# WebCamera.net
KiCad netlist of a schematic drawn in Altium Designer
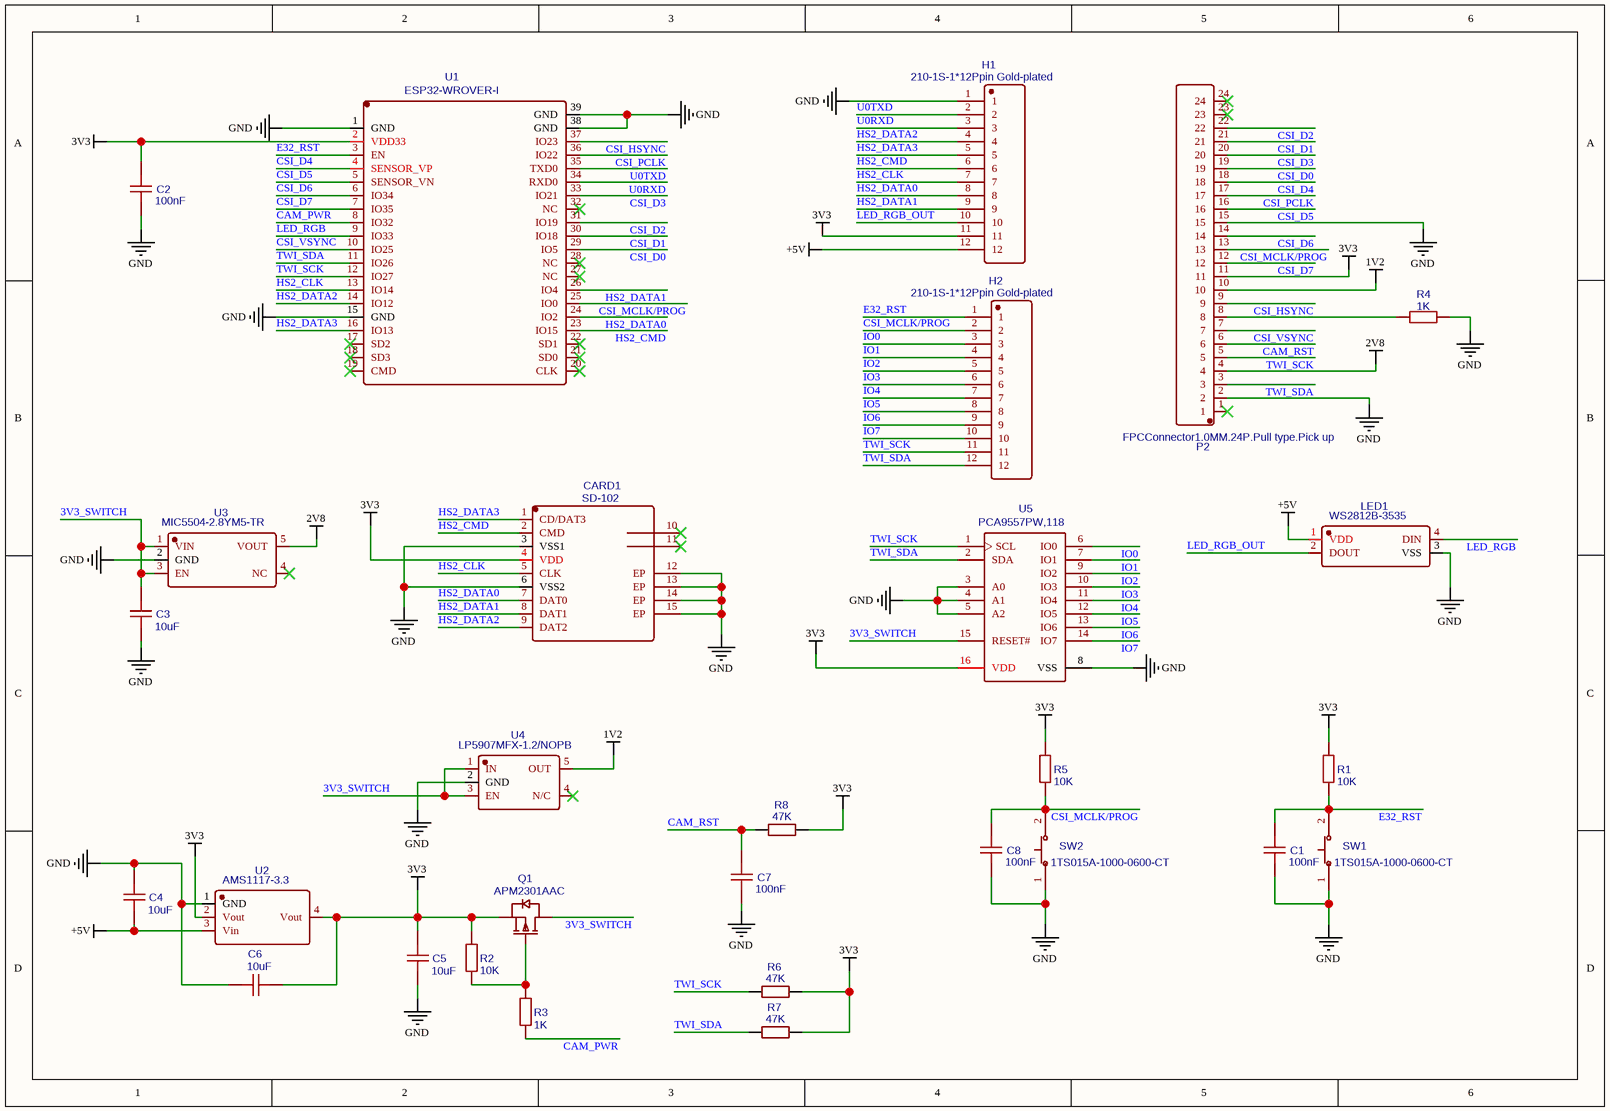
[diagram p0: WebCamera.schdoc]

(export (version "E")
  (design (tool "Eeschema 10.0.6"))
  (components
    (comp (ref "C1")
      (value "100nF")
      (fields
        (field (name "BOM_SUPPLIER PART") "C307331")
        (field (name "BOM_MANUFACTURER PART") "CL05B104KB54PNC")
        (field (name "CONTRIBUTOR") "LCSC")
      )
      (libsource (lib "altium-import") (part "root_1_100nF_"))
    )
    (comp (ref "C2")
      (value "100nF")
      (fields
        (field (name "BOM_SUPPLIER PART") "C307331")
        (field (name "BOM_MANUFACTURER PART") "CL05B104KB54PNC")
        (field (name "CONTRIBUTOR") "LCSC")
      )
      (libsource (lib "altium-import") (part "root_1_100nF_"))
    )
    (comp (ref "C3")
      (value "10uF")
      (fields
        (field (name "BOM_MANUFACTURER PART") "CL10A106KP8NNNC")
        (field (name "BOM_SUPPLIER PART") "C19702")
      )
      (libsource (lib "altium-import") (part "root_1_10uF_"))
    )
    (comp (ref "C4")
      (value "10uF")
      (fields
        (field (name "BOM_MANUFACTURER PART") "CL10A106KP8NNNC")
        (field (name "BOM_SUPPLIER PART") "C19702")
      )
      (libsource (lib "altium-import") (part "root_1_10uF_"))
    )
    (comp (ref "C5")
      (value "10uF")
      (fields
        (field (name "BOM_MANUFACTURER PART") "CL10A106KP8NNNC")
        (field (name "BOM_SUPPLIER PART") "C19702")
      )
      (libsource (lib "altium-import") (part "root_1_10uF_"))
    )
    (comp (ref "C6")
      (value "10uF")
      (fields
        (field (name "BOM_MANUFACTURER PART") "CL10A106KP8NNNC")
        (field (name "BOM_SUPPLIER PART") "C19702")
      )
      (libsource (lib "altium-import") (part "root_2_10uF_"))
    )
    (comp (ref "C7")
      (value "100nF")
      (fields
        (field (name "BOM_SUPPLIER PART") "C307331")
        (field (name "BOM_MANUFACTURER PART") "CL05B104KB54PNC")
        (field (name "CONTRIBUTOR") "LCSC")
      )
      (libsource (lib "altium-import") (part "root_1_100nF_"))
    )
    (comp (ref "C8")
      (value "100nF")
      (fields
        (field (name "BOM_SUPPLIER PART") "C307331")
        (field (name "BOM_MANUFACTURER PART") "CL05B104KB54PNC")
        (field (name "CONTRIBUTOR") "LCSC")
      )
      (libsource (lib "altium-import") (part "root_1_100nF_"))
    )
    (comp (ref "CARD1")
      (value "SD-102")
      (fields (field (name "BOM_SUPPLIER PART") "C266602") (field (name "CONTRIBUTOR") "LCSC"))
      (libsource (lib "altium-import") (part "root_0_SD-102_"))
    )
    (comp (ref "H1")
      (value "210-1S-1*12Ppin Gold-plated")
      (fields (field (name "BOM_SUPPLIER PART") "C124353") (field (name "CONTRIBUTOR") "LCSC"))
      (libsource (lib "altium-import") (part "root_0_210-1S-1*12Ppin Gold-plated_"))
    )
    (comp (ref "H2")
      (value "210-1S-1*12Ppin Gold-plated")
      (fields (field (name "BOM_SUPPLIER PART") "C124353") (field (name "CONTRIBUTOR") "LCSC"))
      (libsource (lib "altium-import") (part "root_0_210-1S-1*12Ppin Gold-plated_"))
    )
    (comp (ref "LED1")
      (value "WS2812B-3535")
      (fields (field (name "BOM_SUPPLIER PART") "C114583") (field (name "CONTRIBUTOR") "LCSC"))
      (libsource (lib "altium-import") (part "root_0_WS2812B-3535_"))
    )
    (comp (ref "P2")
      (value "FPCConnector1.0MM.24P.Pull type.Pick up")
      (fields (field (name "BOM_SUPPLIER PART") "C34750"))
      (libsource (lib "altium-import") (part "root_0_FPCConnector1.0MM.24P.Pull type.Pick up_"))
    )
    (comp (ref "Q1")
      (value "APM2301AAC")
      (fields (field (name "BOM_SUPPLIER PART") "C475607") (field (name "CONTRIBUTOR") "LCSC"))
      (libsource (lib "altium-import") (part "root_1_APM2301AAC_"))
    )
    (comp (ref "R1")
      (value "10K")
      (fields
        (field (name "BOM_SUPPLIER PART") "C380776")
        (field (name "BOM_MANUFACTURER PART") "SY0805JN10KP")
        (field (name "CONTRIBUTOR") "LCSC")
      )
      (libsource (lib "altium-import") (part "root_1_10K_"))
    )
    (comp (ref "R2")
      (value "10K")
      (fields
        (field (name "BOM_SUPPLIER PART") "C380776")
        (field (name "BOM_MANUFACTURER PART") "SY0805JN10KP")
        (field (name "CONTRIBUTOR") "LCSC")
      )
      (libsource (lib "altium-import") (part "root_1_10K_"))
    )
    (comp (ref "R3")
      (value "1K")
      (fields
        (field (name "BOM_SUPPLIER PART") "C328385")
        (field (name "BOM_MANUFACTURER PART") "AECR0805F1K00K9")
        (field (name "CONTRIBUTOR") "LCSC")
      )
      (libsource (lib "altium-import") (part "root_1_1K_"))
    )
    (comp (ref "R4")
      (value "1K")
      (fields
        (field (name "BOM_SUPPLIER PART") "C328385")
        (field (name "BOM_MANUFACTURER PART") "AECR0805F1K00K9")
        (field (name "CONTRIBUTOR") "LCSC")
      )
      (libsource (lib "altium-import") (part "root_2_1K_"))
    )
    (comp (ref "R5")
      (value "10K")
      (fields
        (field (name "BOM_SUPPLIER PART") "C380776")
        (field (name "BOM_MANUFACTURER PART") "SY0805JN10KP")
        (field (name "CONTRIBUTOR") "LCSC")
      )
      (libsource (lib "altium-import") (part "root_1_10K_"))
    )
    (comp (ref "R6")
      (value "47K")
      (fields
        (field (name "BOM_MANUFACTURER PART") "CR0805J80473G")
        (field (name "BOM_SUPPLIER PART") "C102018")
      )
      (libsource (lib "altium-import") (part "root_0_47K_"))
    )
    (comp (ref "R7")
      (value "47K")
      (fields
        (field (name "BOM_MANUFACTURER PART") "CR0805J80473G")
        (field (name "BOM_SUPPLIER PART") "C102018")
      )
      (libsource (lib "altium-import") (part "root_0_47K_"))
    )
    (comp (ref "R8")
      (value "47K")
      (fields
        (field (name "BOM_MANUFACTURER PART") "CR0805J80473G")
        (field (name "BOM_SUPPLIER PART") "C102018")
      )
      (libsource (lib "altium-import") (part "root_0_47K_"))
    )
    (comp (ref "SW1")
      (value "1TS015A-1000-0600-CT")
      (fields (field (name "BOM_SUPPLIER PART") "C398744") (field (name "CONTRIBUTOR") "LCSC"))
      (libsource (lib "altium-import") (part "root_1_1TS015A-1000-0600-CT_"))
    )
    (comp (ref "SW2")
      (value "1TS015A-1000-0600-CT")
      (fields (field (name "BOM_SUPPLIER PART") "C398744") (field (name "CONTRIBUTOR") "LCSC"))
      (libsource (lib "altium-import") (part "root_1_1TS015A-1000-0600-CT_"))
    )
    (comp (ref "U1")
      (value "ESP32-WROVER-I")
      (fields (field (name "BOM_SUPPLIER PART") "C132370") (field (name "CONTRIBUTOR") "LCSC"))
      (libsource (lib "altium-import") (part "root_0_ESP32-WROVER-I_"))
    )
    (comp (ref "U2")
      (value "AMS1117-3.3")
      (fields (field (name "BOM_SUPPLIER PART") "C6186"))
      (libsource (lib "altium-import") (part "root_0_AMS1117-3.3_"))
    )
    (comp (ref "U3")
      (value "MIC5504-2.8YM5-TR")
      (fields (field (name "BOM_SUPPLIER PART") "C95749") (field (name "CONTRIBUTOR") "LCSC"))
      (libsource (lib "altium-import") (part "root_0_MIC5504-2.8YM5-TR_"))
    )
    (comp (ref "U4")
      (value "LP5907MFX-1.2/NOPB")
      (fields (field (name "BOM_SUPPLIER PART") "C73478") (field (name "CONTRIBUTOR") "LCSC"))
      (libsource (lib "altium-import") (part "root_0_LP5907MFX-1.2/NOPB_"))
    )
    (comp (ref "U5")
      (value "PCA9557PW,118")
      (fields (field (name "BOM_SUPPLIER PART") "C141380") (field (name "CONTRIBUTOR") "LCSC"))
      (libsource (lib "altium-import") (part "root_0_PCA9557PW,118_"))
    )
  )
  (nets
    (net (code "1") (name "+5V") (class "Default")
      (node (ref "C4") (pin "1") (pinfunction "1_1") (pintype "passive"))
      (node (ref "H1") (pin "12") (pinfunction "12_12") (pintype "passive"))
      (node (ref "LED1") (pin "1") (pinfunction "VDD_1") (pintype "passive"))
      (node (ref "U2") (pin "3") (pinfunction "Vin_3") (pintype "passive"))
    )
    (net (code "2") (name "/3V3_SWITCH") (class "Default")
      (node (ref "C3") (pin "2") (pinfunction "2_2") (pintype "passive"))
      (node (ref "Q1") (pin "3") (pinfunction "D_3") (pintype "passive"))
      (node (ref "U3") (pin "1") (pinfunction "VIN_1") (pintype "passive"))
      (node (ref "U3") (pin "3") (pinfunction "EN_3") (pintype "passive"))
      (node (ref "U4") (pin "1") (pinfunction "IN_1") (pintype "passive"))
      (node (ref "U4") (pin "3") (pinfunction "EN_3") (pintype "passive"))
      (node (ref "U5") (pin "15") (pinfunction "RESET#_15") (pintype "passive"))
    )
    (net (code "3") (name "/CAM_PWR") (class "Default")
      (node (ref "R3") (pin "1") (pinfunction "1_1") (pintype "passive"))
      (node (ref "U1") (pin "8") (pinfunction "IO32_8") (pintype "passive"))
    )
    (net (code "4") (name "/CAM_RST") (class "Default")
      (node (ref "C7") (pin "1") (pinfunction "1_1") (pintype "passive"))
      (node (ref "P2") (pin "6") (pinfunction "6_6") (pintype "passive"))
      (node (ref "R8") (pin "1") (pinfunction "1_1") (pintype "passive"))
    )
    (net (code "5") (name "/CSI_D0") (class "Default")
      (node (ref "P2") (pin "19") (pinfunction "19_19") (pintype "passive"))
      (node (ref "U1") (pin "29") (pinfunction "IO5_29") (pintype "passive"))
    )
    (net (code "6") (name "/CSI_D1") (class "Default")
      (node (ref "P2") (pin "21") (pinfunction "21_21") (pintype "passive"))
      (node (ref "U1") (pin "30") (pinfunction "IO18_30") (pintype "passive"))
    )
    (net (code "7") (name "/CSI_D2") (class "Default")
      (node (ref "P2") (pin "22") (pinfunction "22_22") (pintype "passive"))
      (node (ref "U1") (pin "31") (pinfunction "IO19_31") (pintype "passive"))
    )
    (net (code "8") (name "/CSI_D3") (class "Default")
      (node (ref "P2") (pin "20") (pinfunction "20_20") (pintype "passive"))
      (node (ref "U1") (pin "33") (pinfunction "IO21_33") (pintype "passive"))
    )
    (net (code "9") (name "/CSI_D4") (class "Default")
      (node (ref "P2") (pin "18") (pinfunction "18_18") (pintype "passive"))
      (node (ref "U1") (pin "4") (pinfunction "SENSOR_VP_4") (pintype "passive"))
    )
    (net (code "10") (name "/CSI_D5") (class "Default")
      (node (ref "P2") (pin "16") (pinfunction "16_16") (pintype "passive"))
      (node (ref "U1") (pin "5") (pinfunction "SENSOR_VN_5") (pintype "passive"))
    )
    (net (code "11") (name "/CSI_D6") (class "Default")
      (node (ref "P2") (pin "14") (pinfunction "14_14") (pintype "passive"))
      (node (ref "U1") (pin "6") (pinfunction "IO34_6") (pintype "passive"))
    )
    (net (code "12") (name "/CSI_D7") (class "Default")
      (node (ref "P2") (pin "12") (pinfunction "12_12") (pintype "passive"))
      (node (ref "U1") (pin "7") (pinfunction "IO35_7") (pintype "passive"))
    )
    (net (code "13") (name "/CSI_HSYNC") (class "Default")
      (node (ref "P2") (pin "9") (pinfunction "9_9") (pintype "passive"))
      (node (ref "U1") (pin "37") (pinfunction "IO23_37") (pintype "passive"))
    )
    (net (code "14") (name "/CSI_MCLK{slash}PROG") (class "Default")
      (node (ref "C8") (pin "1") (pinfunction "1_1") (pintype "passive"))
      (node (ref "H2") (pin "2") (pinfunction "2_2") (pintype "passive"))
      (node (ref "P2") (pin "13") (pinfunction "13_13") (pintype "passive"))
      (node (ref "R5") (pin "1") (pinfunction "1_1") (pintype "passive"))
      (node (ref "SW2") (pin "2") (pinfunction "2_2") (pintype "passive"))
      (node (ref "U1") (pin "25") (pinfunction "IO0_25") (pintype "passive"))
    )
    (net (code "15") (name "/CSI_PCLK") (class "Default")
      (node (ref "P2") (pin "17") (pinfunction "17_17") (pintype "passive"))
      (node (ref "U1") (pin "36") (pinfunction "IO22_36") (pintype "passive"))
    )
    (net (code "16") (name "/CSI_VSYNC") (class "Default")
      (node (ref "P2") (pin "7") (pinfunction "7_7") (pintype "passive"))
      (node (ref "U1") (pin "10") (pinfunction "IO25_10") (pintype "passive"))
    )
    (net (code "17") (name "/E32_RST") (class "Default")
      (node (ref "C1") (pin "1") (pinfunction "1_1") (pintype "passive"))
      (node (ref "H2") (pin "1") (pinfunction "1_1") (pintype "passive"))
      (node (ref "R1") (pin "1") (pinfunction "1_1") (pintype "passive"))
      (node (ref "SW1") (pin "2") (pinfunction "2_2") (pintype "passive"))
      (node (ref "U1") (pin "3") (pinfunction "EN_3") (pintype "passive"))
    )
    (net (code "18") (name "/HS2_CLK") (class "Default")
      (node (ref "CARD1") (pin "5") (pinfunction "CLK_5") (pintype "passive"))
      (node (ref "H1") (pin "7") (pinfunction "7_7") (pintype "passive"))
      (node (ref "U1") (pin "13") (pinfunction "IO14_13") (pintype "passive"))
    )
    (net (code "19") (name "/HS2_CMD") (class "Default")
      (node (ref "CARD1") (pin "2") (pinfunction "CMD_2") (pintype "passive"))
      (node (ref "H1") (pin "6") (pinfunction "6_6") (pintype "passive"))
      (node (ref "U1") (pin "23") (pinfunction "IO15_23") (pintype "passive"))
    )
    (net (code "20") (name "/HS2_DATA0") (class "Default")
      (node (ref "CARD1") (pin "7") (pinfunction "DAT0_7") (pintype "passive"))
      (node (ref "H1") (pin "8") (pinfunction "8_8") (pintype "passive"))
      (node (ref "U1") (pin "24") (pinfunction "IO2_24") (pintype "passive"))
    )
    (net (code "21") (name "/HS2_DATA1") (class "Default")
      (node (ref "CARD1") (pin "8") (pinfunction "DAT1_8") (pintype "passive"))
      (node (ref "H1") (pin "9") (pinfunction "9_9") (pintype "passive"))
      (node (ref "U1") (pin "26") (pinfunction "IO4_26") (pintype "passive"))
    )
    (net (code "22") (name "/HS2_DATA2") (class "Default")
      (node (ref "CARD1") (pin "9") (pinfunction "DAT2_9") (pintype "passive"))
      (node (ref "H1") (pin "4") (pinfunction "4_4") (pintype "passive"))
      (node (ref "U1") (pin "14") (pinfunction "IO12_14") (pintype "passive"))
    )
    (net (code "23") (name "/HS2_DATA3") (class "Default")
      (node (ref "CARD1") (pin "1") (pinfunction "CD/DAT3_1") (pintype "passive"))
      (node (ref "H1") (pin "5") (pinfunction "5_5") (pintype "passive"))
      (node (ref "U1") (pin "16") (pinfunction "IO13_16") (pintype "passive"))
    )
    (net (code "24") (name "/IO0") (class "Default")
      (node (ref "H2") (pin "3") (pinfunction "3_3") (pintype "passive"))
      (node (ref "U5") (pin "6") (pinfunction "IO0_6") (pintype "passive"))
    )
    (net (code "25") (name "/IO1") (class "Default")
      (node (ref "H2") (pin "4") (pinfunction "4_4") (pintype "passive"))
      (node (ref "U5") (pin "7") (pinfunction "IO1_7") (pintype "passive"))
    )
    (net (code "26") (name "/IO2") (class "Default")
      (node (ref "H2") (pin "5") (pinfunction "5_5") (pintype "passive"))
      (node (ref "U5") (pin "9") (pinfunction "IO2_9") (pintype "passive"))
    )
    (net (code "27") (name "/IO3") (class "Default")
      (node (ref "H2") (pin "6") (pinfunction "6_6") (pintype "passive"))
      (node (ref "U5") (pin "10") (pinfunction "IO3_10") (pintype "passive"))
    )
    (net (code "28") (name "/IO4") (class "Default")
      (node (ref "H2") (pin "7") (pinfunction "7_7") (pintype "passive"))
      (node (ref "U5") (pin "11") (pinfunction "IO4_11") (pintype "passive"))
    )
    (net (code "29") (name "/IO5") (class "Default")
      (node (ref "H2") (pin "8") (pinfunction "8_8") (pintype "passive"))
      (node (ref "U5") (pin "12") (pinfunction "IO5_12") (pintype "passive"))
    )
    (net (code "30") (name "/IO6") (class "Default")
      (node (ref "H2") (pin "9") (pinfunction "9_9") (pintype "passive"))
      (node (ref "U5") (pin "13") (pinfunction "IO6_13") (pintype "passive"))
    )
    (net (code "31") (name "/IO7") (class "Default")
      (node (ref "H2") (pin "10") (pinfunction "10_10") (pintype "passive"))
      (node (ref "U5") (pin "14") (pinfunction "IO7_14") (pintype "passive"))
    )
    (net (code "32") (name "/LED_RGB") (class "Default")
      (node (ref "LED1") (pin "4") (pinfunction "DIN_4") (pintype "passive"))
      (node (ref "U1") (pin "9") (pinfunction "IO33_9") (pintype "passive"))
    )
    (net (code "33") (name "/LED_RGB_OUT") (class "Default")
      (node (ref "H1") (pin "10") (pinfunction "10_10") (pintype "passive"))
      (node (ref "LED1") (pin "2") (pinfunction "DOUT_2") (pintype "passive"))
    )
    (net (code "34") (name "/TWI_SCK") (class "Default")
      (node (ref "H2") (pin "11") (pinfunction "11_11") (pintype "passive"))
      (node (ref "P2") (pin "5") (pinfunction "5_5") (pintype "passive"))
      (node (ref "R6") (pin "1") (pinfunction "1_1") (pintype "passive"))
      (node (ref "U1") (pin "12") (pinfunction "IO27_12") (pintype "passive"))
      (node (ref "U5") (pin "1") (pinfunction "SCL_1") (pintype "passive"))
    )
    (net (code "35") (name "/TWI_SDA") (class "Default")
      (node (ref "H2") (pin "12") (pinfunction "12_12") (pintype "passive"))
      (node (ref "P2") (pin "3") (pinfunction "3_3") (pintype "passive"))
      (node (ref "R7") (pin "1") (pinfunction "1_1") (pintype "passive"))
      (node (ref "U1") (pin "11") (pinfunction "IO26_11") (pintype "passive"))
      (node (ref "U5") (pin "2") (pinfunction "SDA_2") (pintype "passive"))
    )
    (net (code "36") (name "/U0RXD") (class "Default")
      (node (ref "H1") (pin "3") (pinfunction "3_3") (pintype "passive"))
      (node (ref "U1") (pin "34") (pinfunction "RXD0_34") (pintype "passive"))
    )
    (net (code "37") (name "/U0TXD") (class "Default")
      (node (ref "H1") (pin "2") (pinfunction "2_2") (pintype "passive"))
      (node (ref "U1") (pin "35") (pinfunction "TXD0_35") (pintype "passive"))
    )
    (net (code "38") (name "1V2") (class "Default")
      (node (ref "P2") (pin "10") (pinfunction "10_10") (pintype "passive"))
      (node (ref "U4") (pin "5") (pinfunction "OUT_5") (pintype "passive"))
    )
    (net (code "39") (name "2V8") (class "Default")
      (node (ref "P2") (pin "4") (pinfunction "4_4") (pintype "passive"))
      (node (ref "U3") (pin "5") (pinfunction "VOUT_5") (pintype "passive"))
    )
    (net (code "40") (name "3V3") (class "Default")
      (node (ref "C2") (pin "1") (pinfunction "1_1") (pintype "passive"))
      (node (ref "C5") (pin "2") (pinfunction "2_2") (pintype "passive"))
      (node (ref "C6") (pin "1") (pinfunction "1_1") (pintype "passive"))
      (node (ref "CARD1") (pin "4") (pinfunction "VDD_4") (pintype "passive"))
      (node (ref "H1") (pin "11") (pinfunction "11_11") (pintype "passive"))
      (node (ref "P2") (pin "11") (pinfunction "11_11") (pintype "passive"))
      (node (ref "Q1") (pin "2") (pinfunction "S_2") (pintype "passive"))
      (node (ref "R1") (pin "2") (pinfunction "2_2") (pintype "passive"))
      (node (ref "R2") (pin "2") (pinfunction "2_2") (pintype "passive"))
      (node (ref "R5") (pin "2") (pinfunction "2_2") (pintype "passive"))
      (node (ref "R6") (pin "2") (pinfunction "2_2") (pintype "passive"))
      (node (ref "R7") (pin "2") (pinfunction "2_2") (pintype "passive"))
      (node (ref "R8") (pin "2") (pinfunction "2_2") (pintype "passive"))
      (node (ref "U1") (pin "2") (pinfunction "VDD33_2") (pintype "passive"))
      (node (ref "U2") (pin "2") (pinfunction "Vout_2") (pintype "passive"))
      (node (ref "U2") (pin "4") (pinfunction "Vout_4") (pintype "passive"))
      (node (ref "U5") (pin "16") (pinfunction "VDD_16") (pintype "passive"))
    )
    (net (code "41") (name "GND") (class "Default")
      (node (ref "C1") (pin "2") (pinfunction "2_2") (pintype "passive"))
      (node (ref "C2") (pin "2") (pinfunction "2_2") (pintype "passive"))
      (node (ref "C3") (pin "1") (pinfunction "1_1") (pintype "passive"))
      (node (ref "C4") (pin "2") (pinfunction "2_2") (pintype "passive"))
      (node (ref "C5") (pin "1") (pinfunction "1_1") (pintype "passive"))
      (node (ref "C6") (pin "2") (pinfunction "2_2") (pintype "passive"))
      (node (ref "C7") (pin "2") (pinfunction "2_2") (pintype "passive"))
      (node (ref "C8") (pin "2") (pinfunction "2_2") (pintype "passive"))
      (node (ref "CARD1") (pin "12") (pinfunction "EP_12") (pintype "passive"))
      (node (ref "CARD1") (pin "13") (pinfunction "EP_13") (pintype "passive"))
      (node (ref "CARD1") (pin "14") (pinfunction "EP_14") (pintype "passive"))
      (node (ref "CARD1") (pin "15") (pinfunction "EP_15") (pintype "passive"))
      (node (ref "CARD1") (pin "3") (pinfunction "VSS1_3") (pintype "passive"))
      (node (ref "CARD1") (pin "6") (pinfunction "VSS2_6") (pintype "passive"))
      (node (ref "H1") (pin "1") (pinfunction "1_1") (pintype "passive"))
      (node (ref "LED1") (pin "3") (pinfunction "VSS_3") (pintype "passive"))
      (node (ref "P2") (pin "15") (pinfunction "15_15") (pintype "passive"))
      (node (ref "P2") (pin "2") (pinfunction "2_2") (pintype "passive"))
      (node (ref "R4") (pin "1") (pinfunction "1_1") (pintype "passive"))
      (node (ref "SW1") (pin "1") (pinfunction "1_1") (pintype "passive"))
      (node (ref "SW2") (pin "1") (pinfunction "1_1") (pintype "passive"))
      (node (ref "U1") (pin "1") (pinfunction "GND_1") (pintype "passive"))
      (node (ref "U1") (pin "15") (pinfunction "GND_15") (pintype "passive"))
      (node (ref "U1") (pin "38") (pinfunction "GND_38") (pintype "passive"))
      (node (ref "U1") (pin "39") (pinfunction "GND_39") (pintype "passive"))
      (node (ref "U2") (pin "1") (pinfunction "GND_1") (pintype "passive"))
      (node (ref "U3") (pin "2") (pinfunction "GND_2") (pintype "passive"))
      (node (ref "U4") (pin "2") (pinfunction "GND_2") (pintype "passive"))
      (node (ref "U5") (pin "3") (pinfunction "A0_3") (pintype "passive"))
      (node (ref "U5") (pin "4") (pinfunction "A1_4") (pintype "passive"))
      (node (ref "U5") (pin "5") (pinfunction "A2_5") (pintype "passive"))
      (node (ref "U5") (pin "8") (pinfunction "VSS_8") (pintype "passive"))
    )
    (net (code "42") (name "Net-(P2-Pad8)") (class "Default")
      (node (ref "P2") (pin "8") (pinfunction "8_8") (pintype "passive"))
      (node (ref "R4") (pin "2") (pinfunction "2_2") (pintype "passive"))
    )
    (net (code "43") (name "Net-(Q1-G)") (class "Default")
      (node (ref "Q1") (pin "1") (pinfunction "G_1") (pintype "passive"))
      (node (ref "R2") (pin "1") (pinfunction "1_1") (pintype "passive"))
      (node (ref "R3") (pin "2") (pinfunction "2_2") (pintype "passive"))
    )
    (net (code "44") (name "unconnected-(CARD1-Pad10)") (class "Default")
      (node (ref "CARD1") (pin "10") (pinfunction "10_10") (pintype "passive+no_connect"))
    )
    (net (code "45") (name "unconnected-(CARD1-Pad11)") (class "Default")
      (node (ref "CARD1") (pin "11") (pinfunction "11_11") (pintype "passive+no_connect"))
    )
    (net (code "46") (name "unconnected-(P2-Pad1)") (class "Default")
      (node (ref "P2") (pin "1") (pinfunction "1_1") (pintype "passive+no_connect"))
    )
    (net (code "47") (name "unconnected-(P2-Pad23)") (class "Default")
      (node (ref "P2") (pin "23") (pinfunction "23_23") (pintype "passive+no_connect"))
    )
    (net (code "48") (name "unconnected-(P2-Pad24)") (class "Default")
      (node (ref "P2") (pin "24") (pinfunction "24_24") (pintype "passive+no_connect"))
    )
    (net (code "49") (name "unconnected-(U1-CLK-Pad20)") (class "Default")
      (node (ref "U1") (pin "20") (pinfunction "CLK_20") (pintype "passive+no_connect"))
    )
    (net (code "50") (name "unconnected-(U1-CMD-Pad19)") (class "Default")
      (node (ref "U1") (pin "19") (pinfunction "CMD_19") (pintype "passive+no_connect"))
    )
    (net (code "51") (name "unconnected-(U1-NC-Pad27)") (class "Default")
      (node (ref "U1") (pin "27") (pinfunction "NC_27") (pintype "passive+no_connect"))
    )
    (net (code "52") (name "unconnected-(U1-NC-Pad28)") (class "Default")
      (node (ref "U1") (pin "28") (pinfunction "NC_28") (pintype "passive+no_connect"))
    )
    (net (code "53") (name "unconnected-(U1-NC-Pad32)") (class "Default")
      (node (ref "U1") (pin "32") (pinfunction "NC_32") (pintype "passive+no_connect"))
    )
    (net (code "54") (name "unconnected-(U1-SD0-Pad21)") (class "Default")
      (node (ref "U1") (pin "21") (pinfunction "SD0_21") (pintype "passive+no_connect"))
    )
    (net (code "55") (name "unconnected-(U1-SD1-Pad22)") (class "Default")
      (node (ref "U1") (pin "22") (pinfunction "SD1_22") (pintype "passive+no_connect"))
    )
    (net (code "56") (name "unconnected-(U1-SD2-Pad17)") (class "Default")
      (node (ref "U1") (pin "17") (pinfunction "SD2_17") (pintype "passive+no_connect"))
    )
    (net (code "57") (name "unconnected-(U1-SD3-Pad18)") (class "Default")
      (node (ref "U1") (pin "18") (pinfunction "SD3_18") (pintype "passive+no_connect"))
    )
    (net (code "58") (name "unconnected-(U3-NC-Pad4)") (class "Default")
      (node (ref "U3") (pin "4") (pinfunction "NC_4") (pintype "passive+no_connect"))
    )
    (net (code "59") (name "unconnected-(U4-N{slash}C-Pad4)") (class "Default")
      (node (ref "U4") (pin "4") (pinfunction "N/C_4") (pintype "passive+no_connect"))
    )
  )
)
